# control_systemLayout.net
KiCad netlist of a schematic drawn in EAGLE
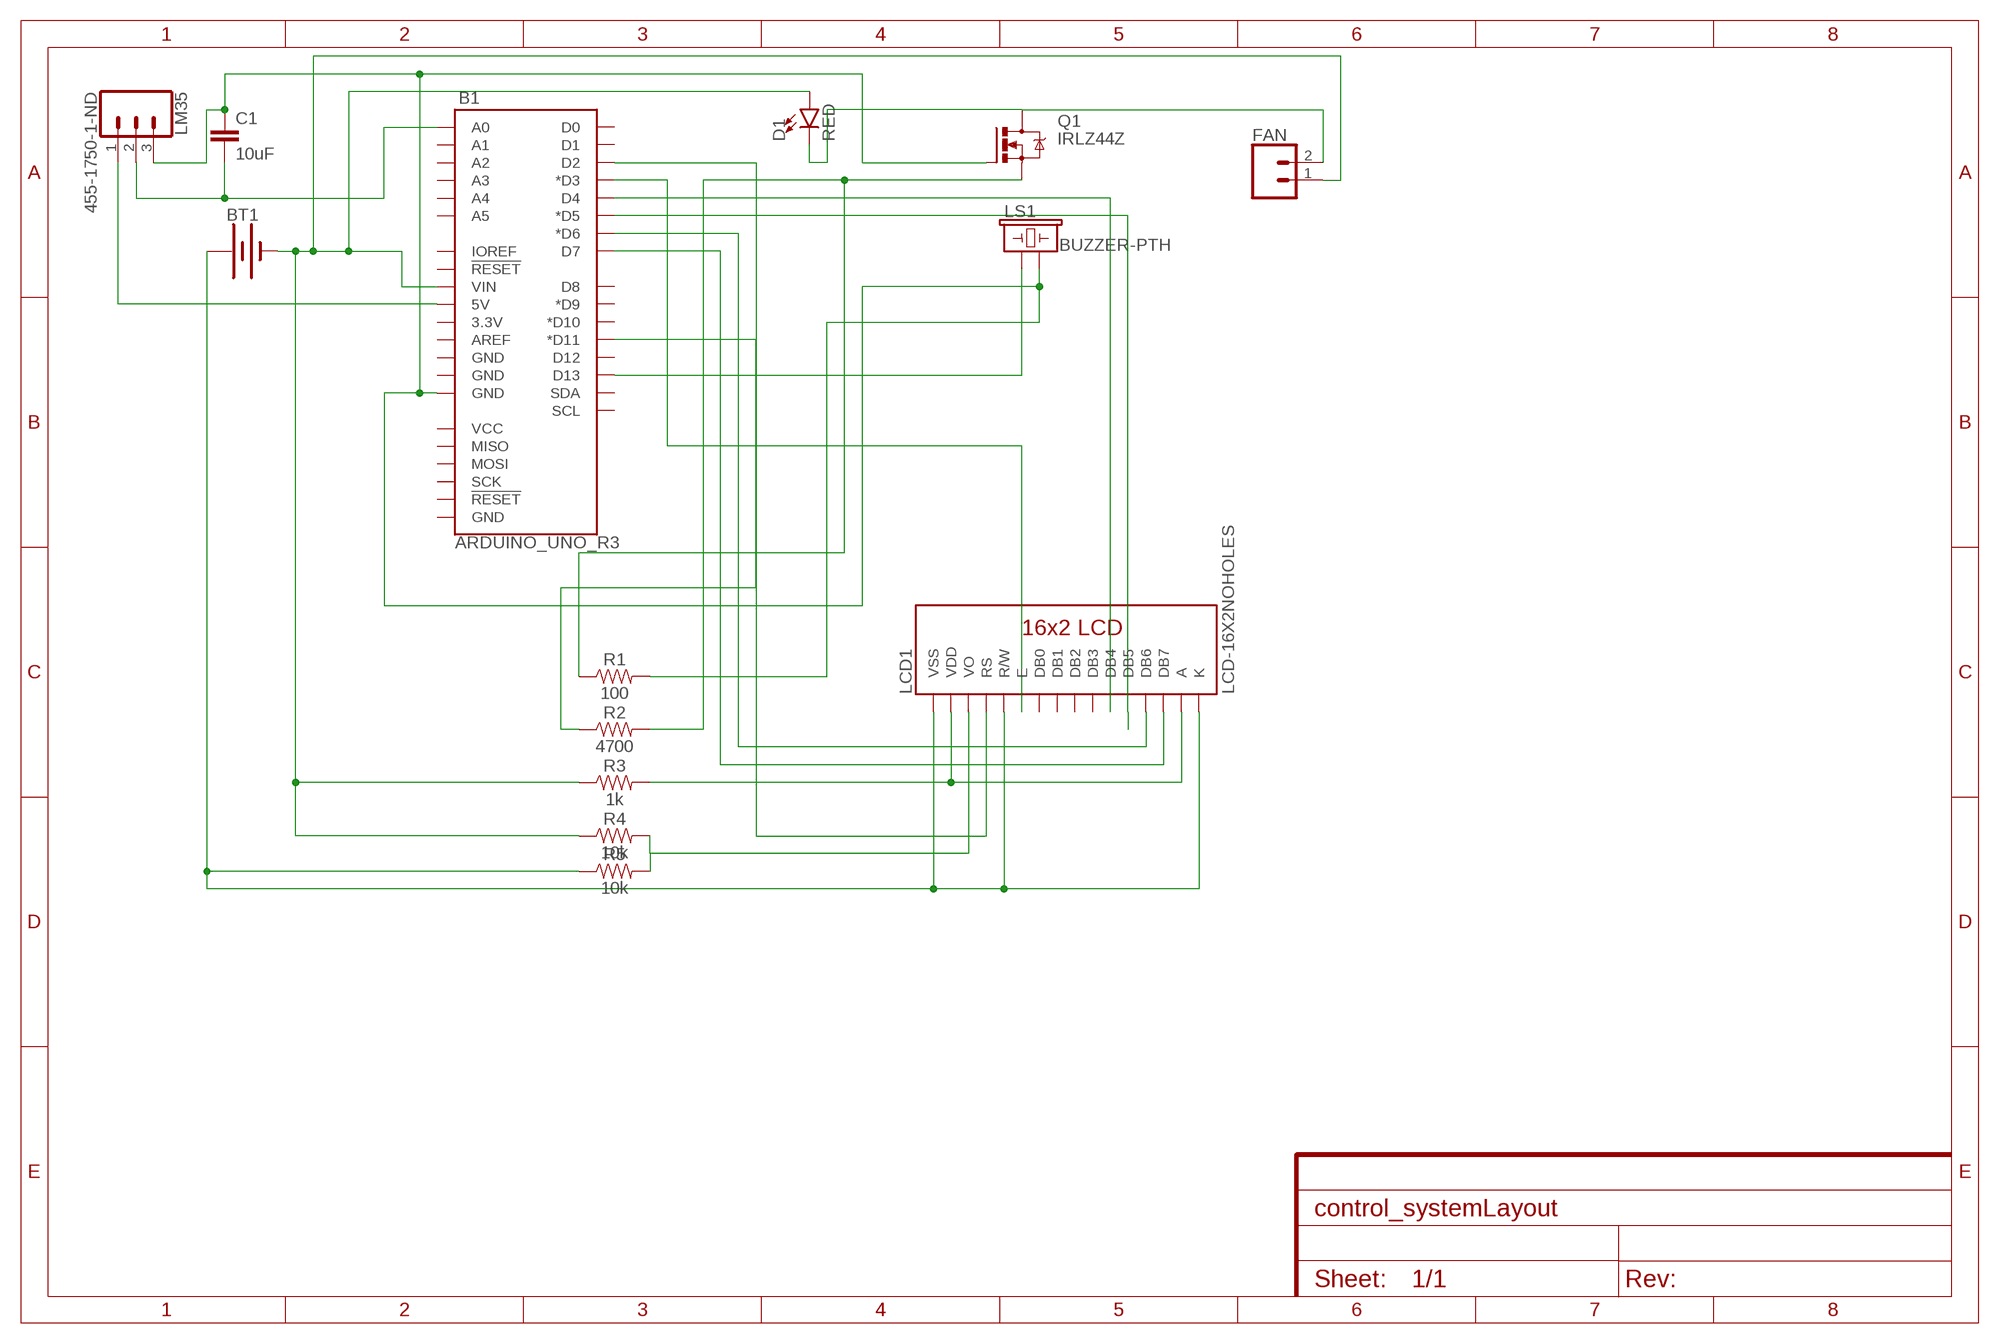
[diagram p0: schematic, sheet 1]

(export (version "E")
  (design (tool "Eeschema 10.0.6"))
  (components
    (comp (ref "B1")
      (value "ARDUINO_UNO_R3")
      (footprint "eagle-import:ARDUINO_R3")
      (libsource (lib "eagle-import") (part "ARDUINO_UNO_R3"))
    )
    (comp (ref "BT1")
      (value "BATTERY-9V")
      (footprint "eagle-import:BATTCON_9V")
      (libsource (lib "eagle-import") (part "BATTERY-9V"))
    )
    (comp (ref "C1")
      (value "10uF")
      (footprint "eagle-import:0603")
      (libsource (lib "eagle-import") (part "0.18UF-0603-10V-10%"))
    )
    (comp (ref "D1")
      (value "RED")
      (footprint "eagle-import:LED-0603")
      (libsource (lib "eagle-import") (part "LED-RED0603"))
    )
    (comp (ref "FAN")
      (value "CONN_02")
      (footprint "eagle-import:1X02")
      (libsource (lib "eagle-import") (part "CONN_02"))
    )
    (comp (ref "LCD1")
      (value "LCD-16X2NOHOLES")
      (footprint "eagle-import:LCD-16X2_NOHOLESNOSILK")
      (libsource (lib "eagle-import") (part "LCD-16X2NOHOLES"))
    )
    (comp (ref "LM35")
      (value "455-1750-1-ND")
      (footprint "eagle-import:1X03")
      (libsource (lib "eagle-import") (part "CONN_03"))
    )
    (comp (ref "LS1")
      (value "BUZZER-PTH")
      (footprint "eagle-import:BUZZER-12MM")
      (libsource (lib "eagle-import") (part "BUZZER-PTH"))
    )
    (comp (ref "Q1")
      (value "IRLZ44Z")
      (footprint "eagle-import:TO220BH")
      (libsource (lib "eagle-import") (part "IRLZ44Z"))
    )
    (comp (ref "R1")
      (value "100")
      (footprint "eagle-import:0603")
      (libsource (lib "eagle-import") (part "0.05OHM-0603-1/5W-1%"))
    )
    (comp (ref "R2")
      (value "4700")
      (footprint "eagle-import:0603")
      (libsource (lib "eagle-import") (part "0.05OHM-0603-1/5W-1%"))
    )
    (comp (ref "R3")
      (value "1k")
      (footprint "eagle-import:0603")
      (libsource (lib "eagle-import") (part "0.05OHM-0603-1/5W-1%"))
    )
    (comp (ref "R4")
      (value "10k")
      (footprint "eagle-import:0603")
      (libsource (lib "eagle-import") (part "0.05OHM-0603-1/5W-1%"))
    )
    (comp (ref "R5")
      (value "10k")
      (footprint "eagle-import:0603")
      (libsource (lib "eagle-import") (part "0.05OHM-0603-1/5W-1%"))
    )
  )
  (nets
    (net (code "1") (name "Net-(B1-*D3)") (class "Default")
      (node (ref "B1") (pin "D3") (pinfunction "*D3_D3") (pintype "bidirectional"))
      (node (ref "LCD1") (pin "6") (pinfunction "E_6") (pintype "input"))
    )
    (net (code "2") (name "Net-(B1-*D5)") (class "Default")
      (node (ref "B1") (pin "D5") (pinfunction "*D5_D5") (pintype "bidirectional"))
      (node (ref "LCD1") (pin "12") (pinfunction "DB5_12") (pintype "bidirectional"))
    )
    (net (code "3") (name "Net-(B1-*D6)") (class "Default")
      (node (ref "B1") (pin "D6") (pinfunction "*D6_D6") (pintype "bidirectional"))
      (node (ref "LCD1") (pin "13") (pinfunction "DB6_13") (pintype "bidirectional"))
    )
    (net (code "4") (name "Net-(B1-*D11)") (class "Default")
      (node (ref "B1") (pin "D11") (pinfunction "*D11_D11") (pintype "bidirectional"))
      (node (ref "R2") (pin "1") (pinfunction "1_1") (pintype "passive"))
    )
    (net (code "5") (name "Net-(B1-Pad5V)") (class "Default")
      (node (ref "B1") (pin "5V") (pinfunction "5V_5V") (pintype "bidirectional"))
      (node (ref "LM35") (pin "1") (pinfunction "1_1") (pintype "passive"))
    )
    (net (code "6") (name "Net-(B1-PadA0)") (class "Default")
      (node (ref "B1") (pin "A0") (pinfunction "A0_A0") (pintype "bidirectional"))
      (node (ref "C1") (pin "2") (pinfunction "2_2") (pintype "passive"))
      (node (ref "LM35") (pin "2") (pinfunction "2_2") (pintype "passive"))
    )
    (net (code "7") (name "Net-(B1-PadVIN)") (class "Default")
      (node (ref "B1") (pin "VIN") (pinfunction "VIN_VIN") (pintype "bidirectional"))
      (node (ref "BT1") (pin "-") (pinfunction "-_-") (pintype "power_in"))
      (node (ref "D1") (pin "A") (pinfunction "A_A") (pintype "passive"))
      (node (ref "FAN") (pin "1") (pinfunction "1_1") (pintype "passive"))
      (node (ref "R3") (pin "1") (pinfunction "1_1") (pintype "passive"))
      (node (ref "R4") (pin "1") (pinfunction "1_1") (pintype "passive"))
    )
    (net (code "8") (name "Net-(D1-PadC)") (class "Default")
      (node (ref "D1") (pin "C") (pinfunction "C_C") (pintype "passive"))
      (node (ref "FAN") (pin "2") (pinfunction "2_2") (pintype "passive"))
      (node (ref "Q1") (pin "D") (pinfunction "D_D") (pintype "passive"))
    )
    (net (code "9") (name "Net-(LCD1-A)") (class "Default")
      (node (ref "LCD1") (pin "15") (pinfunction "A_15") (pintype "power_in"))
      (node (ref "LCD1") (pin "2") (pinfunction "VDD_2") (pintype "power_in"))
      (node (ref "R3") (pin "2") (pinfunction "2_2") (pintype "passive"))
    )
    (net (code "10") (name "Net-(LCD1-DB4)") (class "Default")
      (node (ref "B1") (pin "D4") (pinfunction "D4_D4") (pintype "bidirectional"))
      (node (ref "LCD1") (pin "11") (pinfunction "DB4_11") (pintype "bidirectional"))
    )
    (net (code "11") (name "Net-(LCD1-DB7)") (class "Default")
      (node (ref "B1") (pin "D7") (pinfunction "D7_D7") (pintype "bidirectional"))
      (node (ref "LCD1") (pin "14") (pinfunction "DB7_14") (pintype "bidirectional"))
    )
    (net (code "12") (name "Net-(LCD1-K)") (class "Default")
      (node (ref "BT1") (pin "+") (pinfunction "+_+") (pintype "power_in"))
      (node (ref "LCD1") (pin "1") (pinfunction "VSS_1") (pintype "power_in"))
      (node (ref "LCD1") (pin "16") (pinfunction "K_16") (pintype "power_in"))
      (node (ref "LCD1") (pin "5") (pinfunction "R/W_5") (pintype "input"))
      (node (ref "R5") (pin "1") (pinfunction "1_1") (pintype "passive"))
    )
    (net (code "13") (name "Net-(LCD1-RS)") (class "Default")
      (node (ref "B1") (pin "D2") (pinfunction "D2_D2") (pintype "bidirectional"))
      (node (ref "LCD1") (pin "4") (pinfunction "RS_4") (pintype "input"))
    )
    (net (code "14") (name "Net-(LCD1-VO)") (class "Default")
      (node (ref "LCD1") (pin "3") (pinfunction "VO_3") (pintype "bidirectional"))
      (node (ref "R4") (pin "2") (pinfunction "2_2") (pintype "passive"))
      (node (ref "R5") (pin "2") (pinfunction "2_2") (pintype "passive"))
    )
    (net (code "15") (name "Net-(LS1-1)") (class "Default")
      (node (ref "B1") (pin "D13") (pinfunction "D13_D13") (pintype "bidirectional"))
      (node (ref "LS1") (pin "+") (pinfunction "1_+") (pintype "passive"))
    )
    (net (code "16") (name "Net-(LS1-2)") (class "Default")
      (node (ref "B1") (pin "GND@2") (pinfunction "GND_GND@2") (pintype "bidirectional"))
      (node (ref "C1") (pin "1") (pinfunction "1_1") (pintype "passive"))
      (node (ref "LM35") (pin "3") (pinfunction "3_3") (pintype "passive"))
      (node (ref "LS1") (pin "-") (pinfunction "2_-") (pintype "passive"))
      (node (ref "Q1") (pin "G") (pinfunction "G_G") (pintype "passive"))
      (node (ref "R1") (pin "2") (pinfunction "2_2") (pintype "passive"))
    )
    (net (code "17") (name "Net-(Q1-PadS)") (class "Default")
      (node (ref "Q1") (pin "S") (pinfunction "S_S") (pintype "passive"))
      (node (ref "R1") (pin "1") (pinfunction "1_1") (pintype "passive"))
      (node (ref "R2") (pin "2") (pinfunction "2_2") (pintype "passive"))
    )
    (net (code "18") (name "unconnected-(B1-*D9-PadD9)") (class "Default")
      (node (ref "B1") (pin "D9") (pinfunction "*D9_D9") (pintype "bidirectional"))
    )
    (net (code "19") (name "unconnected-(B1-*D10-PadD10)") (class "Default")
      (node (ref "B1") (pin "D10") (pinfunction "*D10_D10") (pintype "bidirectional"))
    )
    (net (code "20") (name "unconnected-(B1-GND-PadGND@1)") (class "Default")
      (node (ref "B1") (pin "GND@1") (pinfunction "GND_GND@1") (pintype "bidirectional"))
    )
    (net (code "21") (name "unconnected-(B1-GND-PadGND@3)") (class "Default")
      (node (ref "B1") (pin "GND@3") (pinfunction "GND_GND@3") (pintype "bidirectional"))
    )
    (net (code "22") (name "unconnected-(B1-GND-PadGND@4)") (class "Default")
      (node (ref "B1") (pin "GND@4") (pinfunction "GND_GND@4") (pintype "bidirectional"))
    )
    (net (code "23") (name "unconnected-(B1-Pad3.3V)") (class "Default")
      (node (ref "B1") (pin "3.3V") (pinfunction "3.3V_3.3V") (pintype "bidirectional"))
    )
    (net (code "24") (name "unconnected-(B1-PadA1)") (class "Default")
      (node (ref "B1") (pin "A1") (pinfunction "A1_A1") (pintype "bidirectional"))
    )
    (net (code "25") (name "unconnected-(B1-PadA2)") (class "Default")
      (node (ref "B1") (pin "A2") (pinfunction "A2_A2") (pintype "bidirectional"))
    )
    (net (code "26") (name "unconnected-(B1-PadA3)") (class "Default")
      (node (ref "B1") (pin "A3") (pinfunction "A3_A3") (pintype "bidirectional"))
    )
    (net (code "27") (name "unconnected-(B1-PadA4)") (class "Default")
      (node (ref "B1") (pin "A4") (pinfunction "A4_A4") (pintype "bidirectional"))
    )
    (net (code "28") (name "unconnected-(B1-PadA5)") (class "Default")
      (node (ref "B1") (pin "A5") (pinfunction "A5_A5") (pintype "bidirectional"))
    )
    (net (code "29") (name "unconnected-(B1-PadAREF)") (class "Default")
      (node (ref "B1") (pin "AREF") (pinfunction "AREF_AREF") (pintype "bidirectional"))
    )
    (net (code "30") (name "unconnected-(B1-PadD0)") (class "Default")
      (node (ref "B1") (pin "D0") (pinfunction "D0_D0") (pintype "bidirectional"))
    )
    (net (code "31") (name "unconnected-(B1-PadD1)") (class "Default")
      (node (ref "B1") (pin "D1") (pinfunction "D1_D1") (pintype "bidirectional"))
    )
    (net (code "32") (name "unconnected-(B1-PadD8)") (class "Default")
      (node (ref "B1") (pin "D8") (pinfunction "D8_D8") (pintype "bidirectional"))
    )
    (net (code "33") (name "unconnected-(B1-PadD12)") (class "Default")
      (node (ref "B1") (pin "D12") (pinfunction "D12_D12") (pintype "bidirectional"))
    )
    (net (code "34") (name "unconnected-(B1-PadIOREF)") (class "Default")
      (node (ref "B1") (pin "IOREF") (pinfunction "IOREF_IOREF") (pintype "bidirectional"))
    )
    (net (code "35") (name "unconnected-(B1-PadMISO)") (class "Default")
      (node (ref "B1") (pin "MISO") (pinfunction "MISO_MISO") (pintype "bidirectional"))
    )
    (net (code "36") (name "unconnected-(B1-PadMOSI)") (class "Default")
      (node (ref "B1") (pin "MOSI") (pinfunction "MOSI_MOSI") (pintype "bidirectional"))
    )
    (net (code "37") (name "unconnected-(B1-PadSCK)") (class "Default")
      (node (ref "B1") (pin "SCK") (pinfunction "SCK_SCK") (pintype "bidirectional"))
    )
    (net (code "38") (name "unconnected-(B1-PadSCL)") (class "Default")
      (node (ref "B1") (pin "SCL") (pinfunction "SCL_SCL") (pintype "bidirectional"))
    )
    (net (code "39") (name "unconnected-(B1-PadSDA)") (class "Default")
      (node (ref "B1") (pin "SDA") (pinfunction "SDA_SDA") (pintype "bidirectional"))
    )
    (net (code "40") (name "unconnected-(B1-PadVCC)") (class "Default")
      (node (ref "B1") (pin "VCC") (pinfunction "VCC_VCC") (pintype "bidirectional"))
    )
    (net (code "41") (name "unconnected-(B1-~{RESET}-PadRESET@1)") (class "Default")
      (node (ref "B1") (pin "RESET@1") (pinfunction "~{RESET}_RESET@1") (pintype "bidirectional"))
    )
    (net (code "42") (name "unconnected-(B1-~{RESET}-PadRESET@2)") (class "Default")
      (node (ref "B1") (pin "RESET@2") (pinfunction "~{RESET}_RESET@2") (pintype "bidirectional"))
    )
    (net (code "43") (name "unconnected-(LCD1-DB0-Pad7)") (class "Default")
      (node (ref "LCD1") (pin "7") (pinfunction "DB0_7") (pintype "bidirectional"))
    )
    (net (code "44") (name "unconnected-(LCD1-DB1-Pad8)") (class "Default")
      (node (ref "LCD1") (pin "8") (pinfunction "DB1_8") (pintype "bidirectional"))
    )
    (net (code "45") (name "unconnected-(LCD1-DB2-Pad9)") (class "Default")
      (node (ref "LCD1") (pin "9") (pinfunction "DB2_9") (pintype "bidirectional"))
    )
    (net (code "46") (name "unconnected-(LCD1-DB3-Pad10)") (class "Default")
      (node (ref "LCD1") (pin "10") (pinfunction "DB3_10") (pintype "bidirectional"))
    )
  )
)
